# MCU_Sheet1.net
KiCad netlist of a schematic drawn in Altium Designer
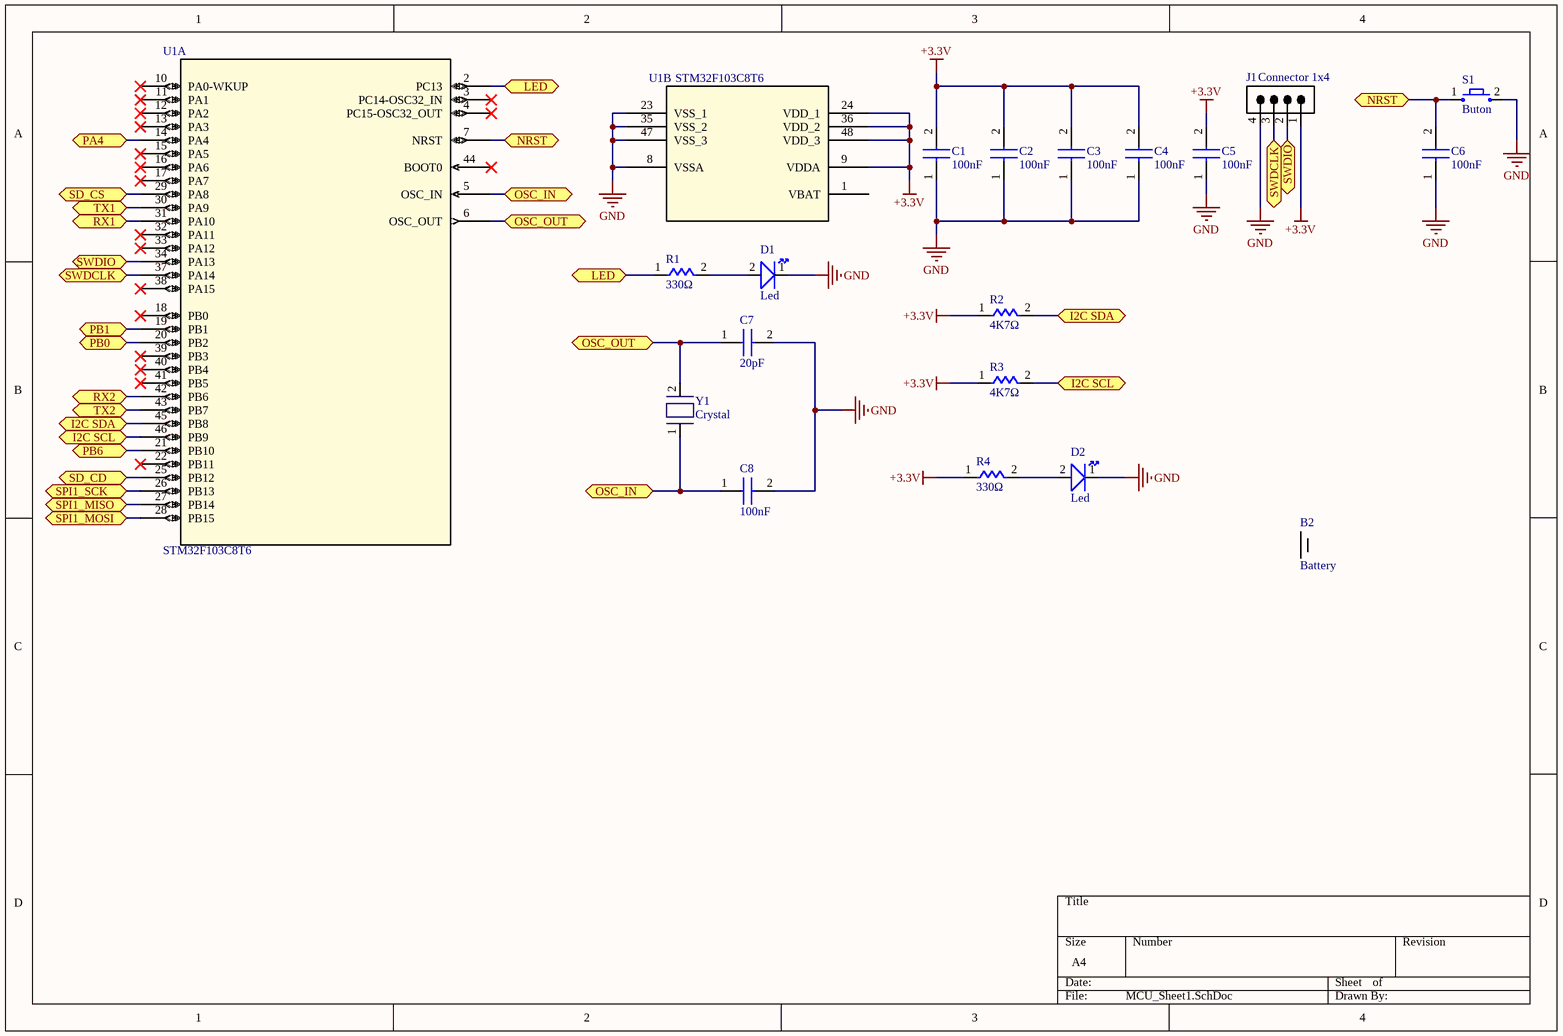
[diagram p0: MCU_Sheet1.SchDoc]

(export (version "E")
  (design (tool "Eeschema 10.0.6"))
  (components
    (comp (ref "B2")
      (value "Battery")
      (footprint "Lityum Battery")
      (libsource (lib "Faydali_Yuk_Schlib1") (part "Battery"))
    )
    (comp (ref "C1")
      (value "100nF")
      (footprint "CAP - 0603")
      (description "Capacitor")
      (libsource (lib "Faydali_Yuk_Schlib1") (part "CAP"))
    )
    (comp (ref "C2")
      (value "100nF")
      (footprint "CAP - 0603")
      (description "Capacitor")
      (libsource (lib "Faydali_Yuk_Schlib1") (part "CAP"))
    )
    (comp (ref "C3")
      (value "100nF")
      (footprint "CAP - 0603")
      (description "Capacitor")
      (libsource (lib "Faydali_Yuk_Schlib1") (part "CAP"))
    )
    (comp (ref "C4")
      (value "100nF")
      (footprint "CAP - 0603")
      (description "Capacitor")
      (libsource (lib "Faydali_Yuk_Schlib1") (part "CAP"))
    )
    (comp (ref "C5")
      (value "100nF")
      (footprint "CAP - 0603")
      (description "Capacitor")
      (libsource (lib "Faydali_Yuk_Schlib1") (part "CAP"))
    )
    (comp (ref "C6")
      (value "100nF")
      (footprint "CAP - 0603")
      (description "Capacitor")
      (libsource (lib "Faydali_Yuk_Schlib1") (part "CAP"))
    )
    (comp (ref "C7")
      (value "20pF")
      (footprint "CAP - 0603")
      (description "Capacitor")
      (libsource (lib "Faydali_Yuk_Schlib1") (part "CAP"))
    )
    (comp (ref "C8")
      (value "100nF")
      (footprint "CAP - 0603")
      (description "Capacitor")
      (libsource (lib "Faydali_Yuk_Schlib1") (part "CAP"))
    )
    (comp (ref "D1")
      (value "Led")
      (footprint "LED - 0603")
      (description "HL-PST-1608U51GC - LED SMD 0603 GREEN 500mcd 120° WATER CLEAR")
      (libsource (lib "Faydali_Yuk_Schlib1") (part "Led"))
    )
    (comp (ref "D2")
      (value "Led")
      (footprint "LED - 0603")
      (description "HL-PST-1608U51GC - LED SMD 0603 GREEN 500mcd 120° WATER CLEAR")
      (libsource (lib "Faydali_Yuk_Schlib1") (part "Led"))
    )
    (comp (ref "J1")
      (value "Connector 1x4")
      (footprint "Connector 1x4")
      (description "MOLEX-705530003 - CONNECTOR HEADER 2.54MM 4P 90C GOLD")
      (libsource (lib "Faydali_Yuk_Schlib1") (part "Connector 1x4"))
    )
    (comp (ref "R1")
      (value "330Ω")
      (footprint "RES - 0603")
      (description "SMD Res")
      (libsource (lib "Faydali_Yuk_Schlib1") (part "Res"))
    )
    (comp (ref "R2")
      (value "4K7Ω")
      (footprint "RES - 0603")
      (description "SMD Res")
      (libsource (lib "Faydali_Yuk_Schlib1") (part "Res"))
    )
    (comp (ref "R3")
      (value "4K7Ω")
      (footprint "RES - 0603")
      (description "SMD Res")
      (libsource (lib "Faydali_Yuk_Schlib1") (part "Res"))
    )
    (comp (ref "R4")
      (value "330Ω")
      (footprint "RES - 0603")
      (description "SMD Res")
      (libsource (lib "Faydali_Yuk_Schlib1") (part "Res"))
    )
    (comp (ref "S1")
      (value "Buton")
      (footprint "Button - DTSMF31RVTR")
      (description "DTSMF-31R-V-T/R - SWITCH TACT 6.00x3.50 4.30mm 260gF SMT V/T")
      (libsource (lib "Faydali_Yuk_Schlib1") (part "Buton"))
    )
    (comp (ref "U1")
      (value "STM32F103C8T6")
      (footprint "LQFP48")
      (description "Microcontroller")
      (fields (field (name "COPYRIGHT") "Copyright (C) 2021 Ultra Librarian. All rights reserved."))
      (libsource (lib "Faydali_Yuk_Schlib1") (part "STM32F103C8T6"))
    )
    (comp (ref "Y1")
      (value "Crystal")
      (footprint "Crystal - HC-49S SMD")
      (description "AS-8.000-18-SMD-TR - CRYSTAL 8.0000MHZ 18PF SMD")
      (libsource (lib "Faydali_Yuk_Schlib1") (part "Crystal"))
    )
  )
  (nets
    (net (code "1") (name "+3.3V") (class "Default")
      (node (ref "C1") (pin "2") (pinfunction "2_2") (pintype "passive"))
      (node (ref "C2") (pin "2") (pinfunction "2_2") (pintype "passive"))
      (node (ref "C3") (pin "2") (pinfunction "2_2") (pintype "passive"))
      (node (ref "C4") (pin "2") (pinfunction "2_2") (pintype "passive"))
      (node (ref "C5") (pin "2") (pinfunction "2_2") (pintype "passive"))
      (node (ref "J1") (pin "1") (pinfunction "1_1") (pintype "passive"))
      (node (ref "R2") (pin "1") (pinfunction "1_1") (pintype "passive"))
      (node (ref "R3") (pin "1") (pinfunction "1_1") (pintype "passive"))
      (node (ref "R4") (pin "1") (pinfunction "1_1") (pintype "passive"))
      (node (ref "U1") (pin "24") (pinfunction "VDD_1_24") (pintype "power_in"))
      (node (ref "U1") (pin "36") (pinfunction "VDD_2_36") (pintype "power_in"))
      (node (ref "U1") (pin "48") (pinfunction "VDD_3_48") (pintype "power_in"))
      (node (ref "U1") (pin "9") (pinfunction "VDDA_9") (pintype "power_in"))
    )
    (net (code "2") (name "/I2C SCL") (class "Default")
      (node (ref "R3") (pin "2") (pinfunction "2_2") (pintype "passive"))
      (node (ref "U1") (pin "46") (pinfunction "PB9_46") (pintype "bidirectional"))
    )
    (net (code "3") (name "/I2C SDA") (class "Default")
      (node (ref "R2") (pin "2") (pinfunction "2_2") (pintype "passive"))
      (node (ref "U1") (pin "45") (pinfunction "PB8_45") (pintype "bidirectional"))
    )
    (net (code "4") (name "/LED") (class "Default")
      (node (ref "R1") (pin "1") (pinfunction "1_1") (pintype "passive"))
      (node (ref "U1") (pin "2") (pinfunction "PC13_2") (pintype "bidirectional"))
    )
    (net (code "5") (name "/NRST") (class "Default")
      (node (ref "C6") (pin "2") (pinfunction "2_2") (pintype "passive"))
      (node (ref "S1") (pin "1") (pinfunction "1_1") (pintype "passive"))
      (node (ref "U1") (pin "7") (pinfunction "NRST_7") (pintype "bidirectional"))
    )
    (net (code "6") (name "/OSC_IN") (class "Default")
      (node (ref "C8") (pin "1") (pinfunction "1_1") (pintype "passive"))
      (node (ref "U1") (pin "5") (pinfunction "OSC_IN_5") (pintype "input"))
      (node (ref "Y1") (pin "1") (pinfunction "1_1") (pintype "passive"))
    )
    (net (code "7") (name "/OSC_OUT") (class "Default")
      (node (ref "C7") (pin "1") (pinfunction "1_1") (pintype "passive"))
      (node (ref "U1") (pin "6") (pinfunction "OSC_OUT_6") (pintype "output"))
      (node (ref "Y1") (pin "2") (pinfunction "2_2") (pintype "passive"))
    )
    (net (code "8") (name "/PA4") (class "Default")
      (node (ref "U1") (pin "14") (pinfunction "PA4_14") (pintype "bidirectional"))
    )
    (net (code "9") (name "/PB0") (class "Default")
      (node (ref "U1") (pin "20") (pinfunction "PB2_20") (pintype "bidirectional"))
    )
    (net (code "10") (name "/PB1") (class "Default")
      (node (ref "U1") (pin "19") (pinfunction "PB1_19") (pintype "bidirectional"))
    )
    (net (code "11") (name "/PB6") (class "Default")
      (node (ref "U1") (pin "21") (pinfunction "PB10_21") (pintype "bidirectional"))
    )
    (net (code "12") (name "/RX1") (class "Default")
      (node (ref "U1") (pin "31") (pinfunction "PA10_31") (pintype "bidirectional"))
    )
    (net (code "13") (name "/RX2") (class "Default")
      (node (ref "U1") (pin "42") (pinfunction "PB6_42") (pintype "bidirectional"))
    )
    (net (code "14") (name "/SD_CD") (class "Default")
      (node (ref "U1") (pin "25") (pinfunction "PB12_25") (pintype "bidirectional"))
    )
    (net (code "15") (name "/SD_CS") (class "Default")
      (node (ref "U1") (pin "29") (pinfunction "PA8_29") (pintype "bidirectional"))
    )
    (net (code "16") (name "/SPI1_MISO") (class "Default")
      (node (ref "U1") (pin "27") (pinfunction "PB14_27") (pintype "bidirectional"))
    )
    (net (code "17") (name "/SPI1_MOSI") (class "Default")
      (node (ref "U1") (pin "28") (pinfunction "PB15_28") (pintype "bidirectional"))
    )
    (net (code "18") (name "/SPI1_SCK") (class "Default")
      (node (ref "U1") (pin "26") (pinfunction "PB13_26") (pintype "bidirectional"))
    )
    (net (code "19") (name "/SWDCLK") (class "Default")
      (node (ref "J1") (pin "3") (pinfunction "3_3") (pintype "passive"))
      (node (ref "U1") (pin "37") (pinfunction "PA14_37") (pintype "bidirectional"))
    )
    (net (code "20") (name "/SWDIO") (class "Default")
      (node (ref "J1") (pin "2") (pinfunction "2_2") (pintype "passive"))
      (node (ref "U1") (pin "34") (pinfunction "PA13_34") (pintype "bidirectional"))
    )
    (net (code "21") (name "/TX1") (class "Default")
      (node (ref "U1") (pin "30") (pinfunction "PA9_30") (pintype "bidirectional"))
    )
    (net (code "22") (name "/TX2") (class "Default")
      (node (ref "U1") (pin "43") (pinfunction "PB7_43") (pintype "bidirectional"))
    )
    (net (code "23") (name "GND") (class "Default")
      (node (ref "C1") (pin "1") (pinfunction "1_1") (pintype "passive"))
      (node (ref "C2") (pin "1") (pinfunction "1_1") (pintype "passive"))
      (node (ref "C3") (pin "1") (pinfunction "1_1") (pintype "passive"))
      (node (ref "C4") (pin "1") (pinfunction "1_1") (pintype "passive"))
      (node (ref "C5") (pin "1") (pinfunction "1_1") (pintype "passive"))
      (node (ref "C6") (pin "1") (pinfunction "1_1") (pintype "passive"))
      (node (ref "C7") (pin "2") (pinfunction "2_2") (pintype "passive"))
      (node (ref "C8") (pin "2") (pinfunction "2_2") (pintype "passive"))
      (node (ref "D1") (pin "1") (pinfunction "1_1") (pintype "passive"))
      (node (ref "D2") (pin "1") (pinfunction "1_1") (pintype "passive"))
      (node (ref "J1") (pin "4") (pinfunction "4_4") (pintype "passive"))
      (node (ref "S1") (pin "2") (pinfunction "2_2") (pintype "passive"))
      (node (ref "U1") (pin "23") (pinfunction "VSS_1_23") (pintype "power_in"))
      (node (ref "U1") (pin "35") (pinfunction "VSS_2_35") (pintype "power_in"))
      (node (ref "U1") (pin "47") (pinfunction "VSS_3_47") (pintype "power_in"))
      (node (ref "U1") (pin "8") (pinfunction "VSSA_8") (pintype "power_in"))
    )
    (net (code "24") (name "Net-(D1-Pad2)") (class "Default")
      (node (ref "D1") (pin "2") (pinfunction "2_2") (pintype "passive"))
      (node (ref "R1") (pin "2") (pinfunction "2_2") (pintype "passive"))
    )
    (net (code "25") (name "Net-(D2-Pad2)") (class "Default")
      (node (ref "D2") (pin "2") (pinfunction "2_2") (pintype "passive"))
      (node (ref "R4") (pin "2") (pinfunction "2_2") (pintype "passive"))
    )
    (net (code "26") (name "unconnected-(U1A-BOOT0-Pad44)") (class "Default")
      (node (ref "U1") (pin "44") (pinfunction "BOOT0_44") (pintype "input+no_connect"))
    )
    (net (code "27") (name "unconnected-(U1A-PA0-WKUP-Pad10)") (class "Default")
      (node (ref "U1") (pin "10") (pinfunction "PA0-WKUP_10") (pintype "bidirectional+no_connect"))
    )
    (net (code "28") (name "unconnected-(U1A-PA1-Pad11)") (class "Default")
      (node (ref "U1") (pin "11") (pinfunction "PA1_11") (pintype "bidirectional+no_connect"))
    )
    (net (code "29") (name "unconnected-(U1A-PA2-Pad12)") (class "Default")
      (node (ref "U1") (pin "12") (pinfunction "PA2_12") (pintype "bidirectional+no_connect"))
    )
    (net (code "30") (name "unconnected-(U1A-PA3-Pad13)") (class "Default")
      (node (ref "U1") (pin "13") (pinfunction "PA3_13") (pintype "bidirectional+no_connect"))
    )
    (net (code "31") (name "unconnected-(U1A-PA5-Pad15)") (class "Default")
      (node (ref "U1") (pin "15") (pinfunction "PA5_15") (pintype "bidirectional+no_connect"))
    )
    (net (code "32") (name "unconnected-(U1A-PA6-Pad16)") (class "Default")
      (node (ref "U1") (pin "16") (pinfunction "PA6_16") (pintype "bidirectional+no_connect"))
    )
    (net (code "33") (name "unconnected-(U1A-PA7-Pad17)") (class "Default")
      (node (ref "U1") (pin "17") (pinfunction "PA7_17") (pintype "bidirectional+no_connect"))
    )
    (net (code "34") (name "unconnected-(U1A-PA11-Pad32)") (class "Default")
      (node (ref "U1") (pin "32") (pinfunction "PA11_32") (pintype "bidirectional+no_connect"))
    )
    (net (code "35") (name "unconnected-(U1A-PA12-Pad33)") (class "Default")
      (node (ref "U1") (pin "33") (pinfunction "PA12_33") (pintype "bidirectional+no_connect"))
    )
    (net (code "36") (name "unconnected-(U1A-PA15-Pad38)") (class "Default")
      (node (ref "U1") (pin "38") (pinfunction "PA15_38") (pintype "bidirectional+no_connect"))
    )
    (net (code "37") (name "unconnected-(U1A-PB0-Pad18)") (class "Default")
      (node (ref "U1") (pin "18") (pinfunction "PB0_18") (pintype "bidirectional+no_connect"))
    )
    (net (code "38") (name "unconnected-(U1A-PB3-Pad39)") (class "Default")
      (node (ref "U1") (pin "39") (pinfunction "PB3_39") (pintype "bidirectional+no_connect"))
    )
    (net (code "39") (name "unconnected-(U1A-PB4-Pad40)") (class "Default")
      (node (ref "U1") (pin "40") (pinfunction "PB4_40") (pintype "bidirectional+no_connect"))
    )
    (net (code "40") (name "unconnected-(U1A-PB5-Pad41)") (class "Default")
      (node (ref "U1") (pin "41") (pinfunction "PB5_41") (pintype "bidirectional+no_connect"))
    )
    (net (code "41") (name "unconnected-(U1A-PB11-Pad22)") (class "Default")
      (node (ref "U1") (pin "22") (pinfunction "PB11_22") (pintype "bidirectional+no_connect"))
    )
    (net (code "42") (name "unconnected-(U1A-PC14-OSC32_IN-Pad3)") (class "Default")
      (node (ref "U1") (pin "3") (pinfunction "PC14-OSC32_IN_3") (pintype "bidirectional+no_connect"))
    )
    (net (code "43") (name "unconnected-(U1A-PC15-OSC32_OUT-Pad4)") (class "Default")
      (node (ref "U1") (pin "4") (pinfunction "PC15-OSC32_OUT_4") (pintype "bidirectional+no_connect"))
    )
    (net (code "44") (name "unconnected-(U1B-VBAT-Pad1)") (class "Default")
      (node (ref "U1") (pin "1") (pinfunction "VBAT_1") (pintype "power_in"))
    )
  )
)
